# dsplolo.net
KiCad netlist of a schematic drawn in EAGLE
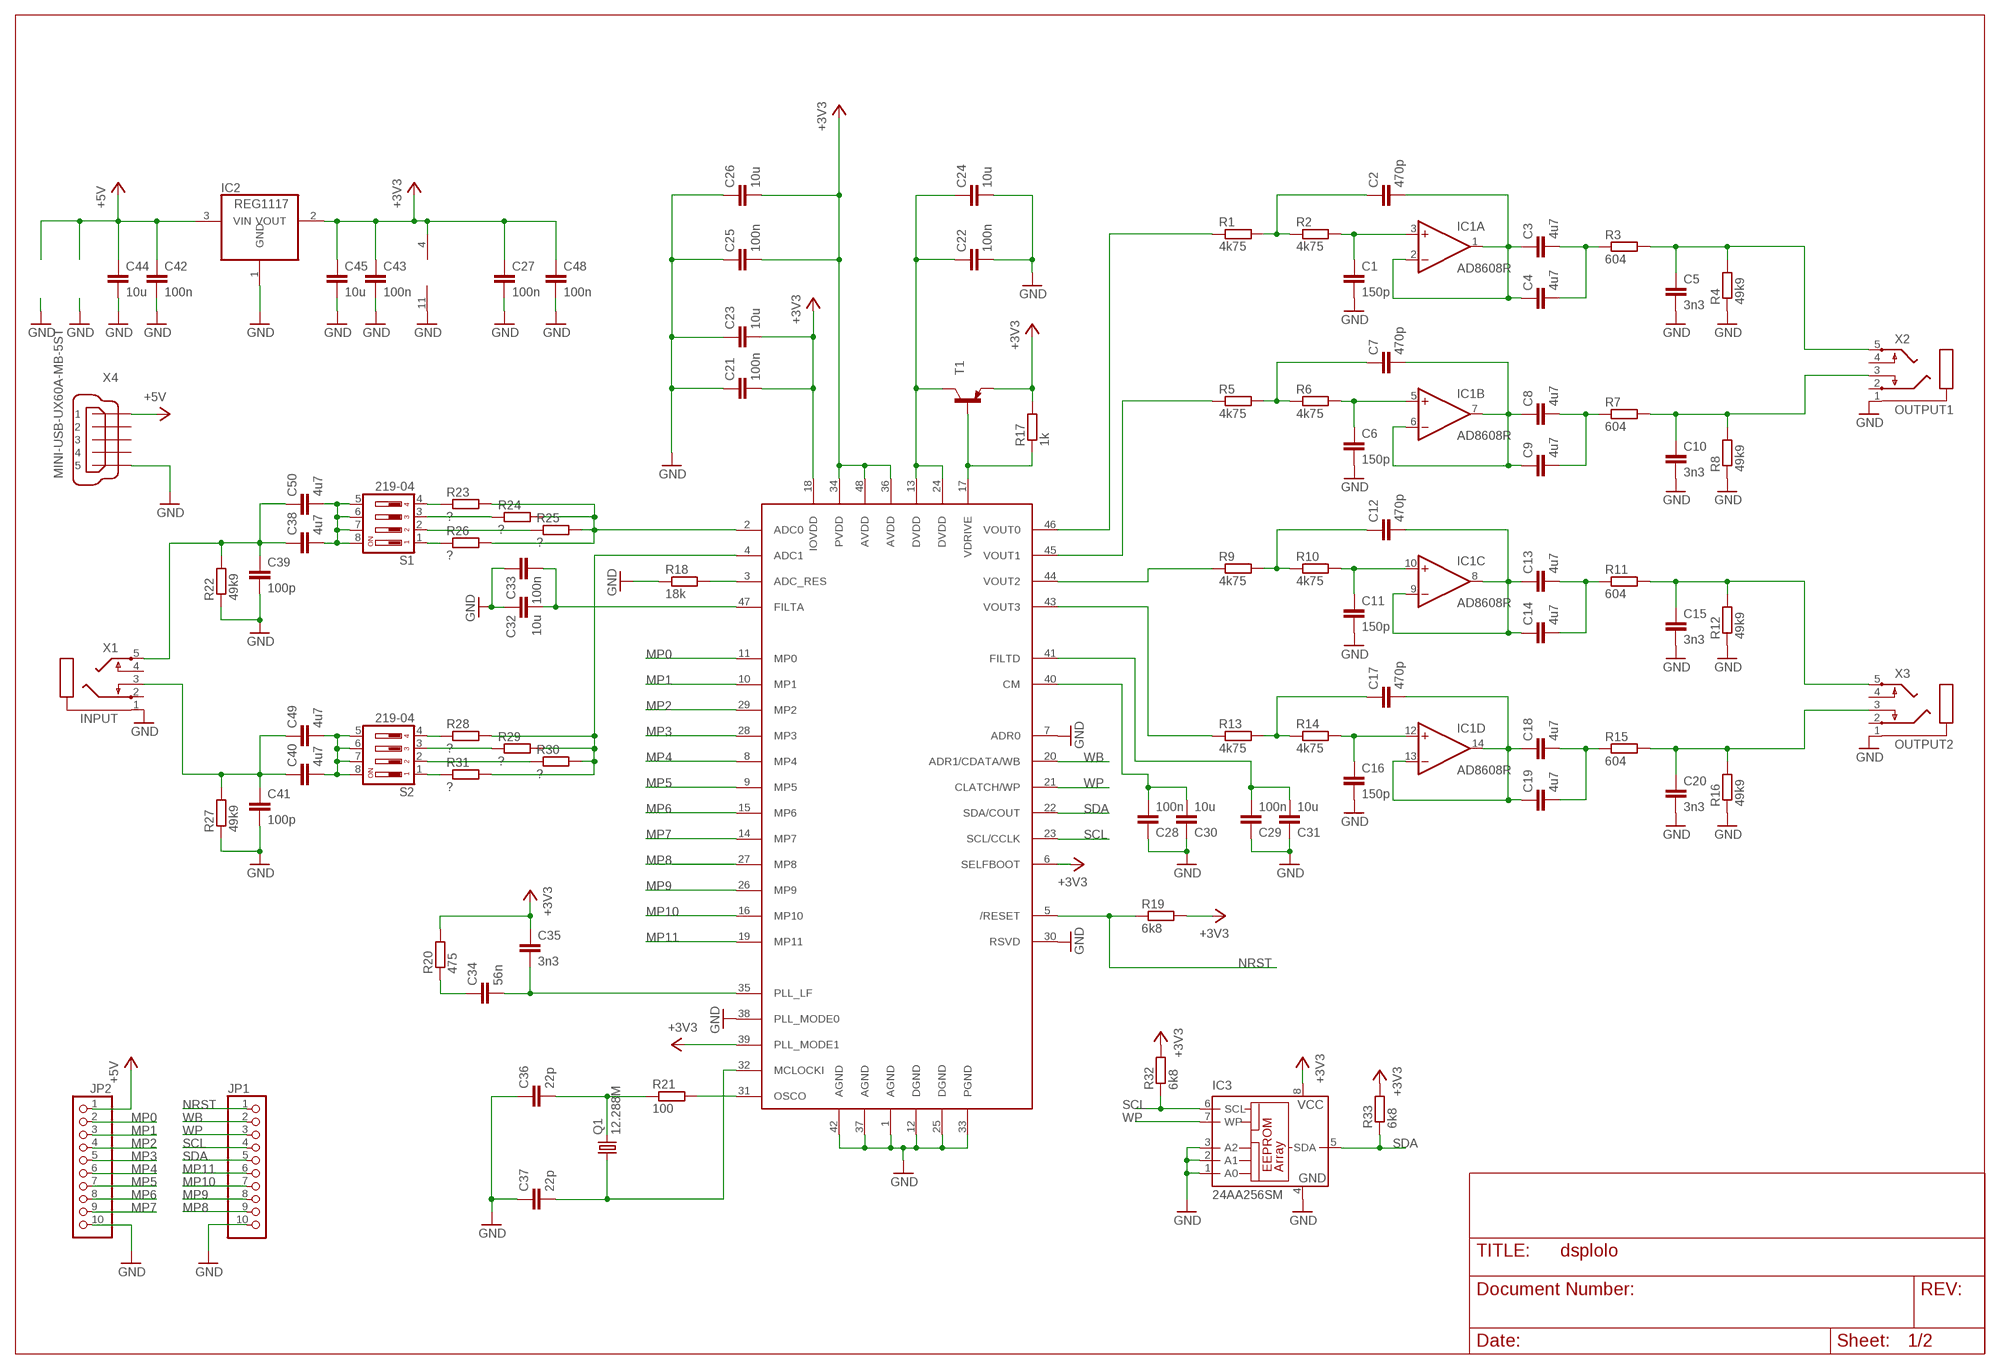
[diagram p0: schematic, sheet 1]
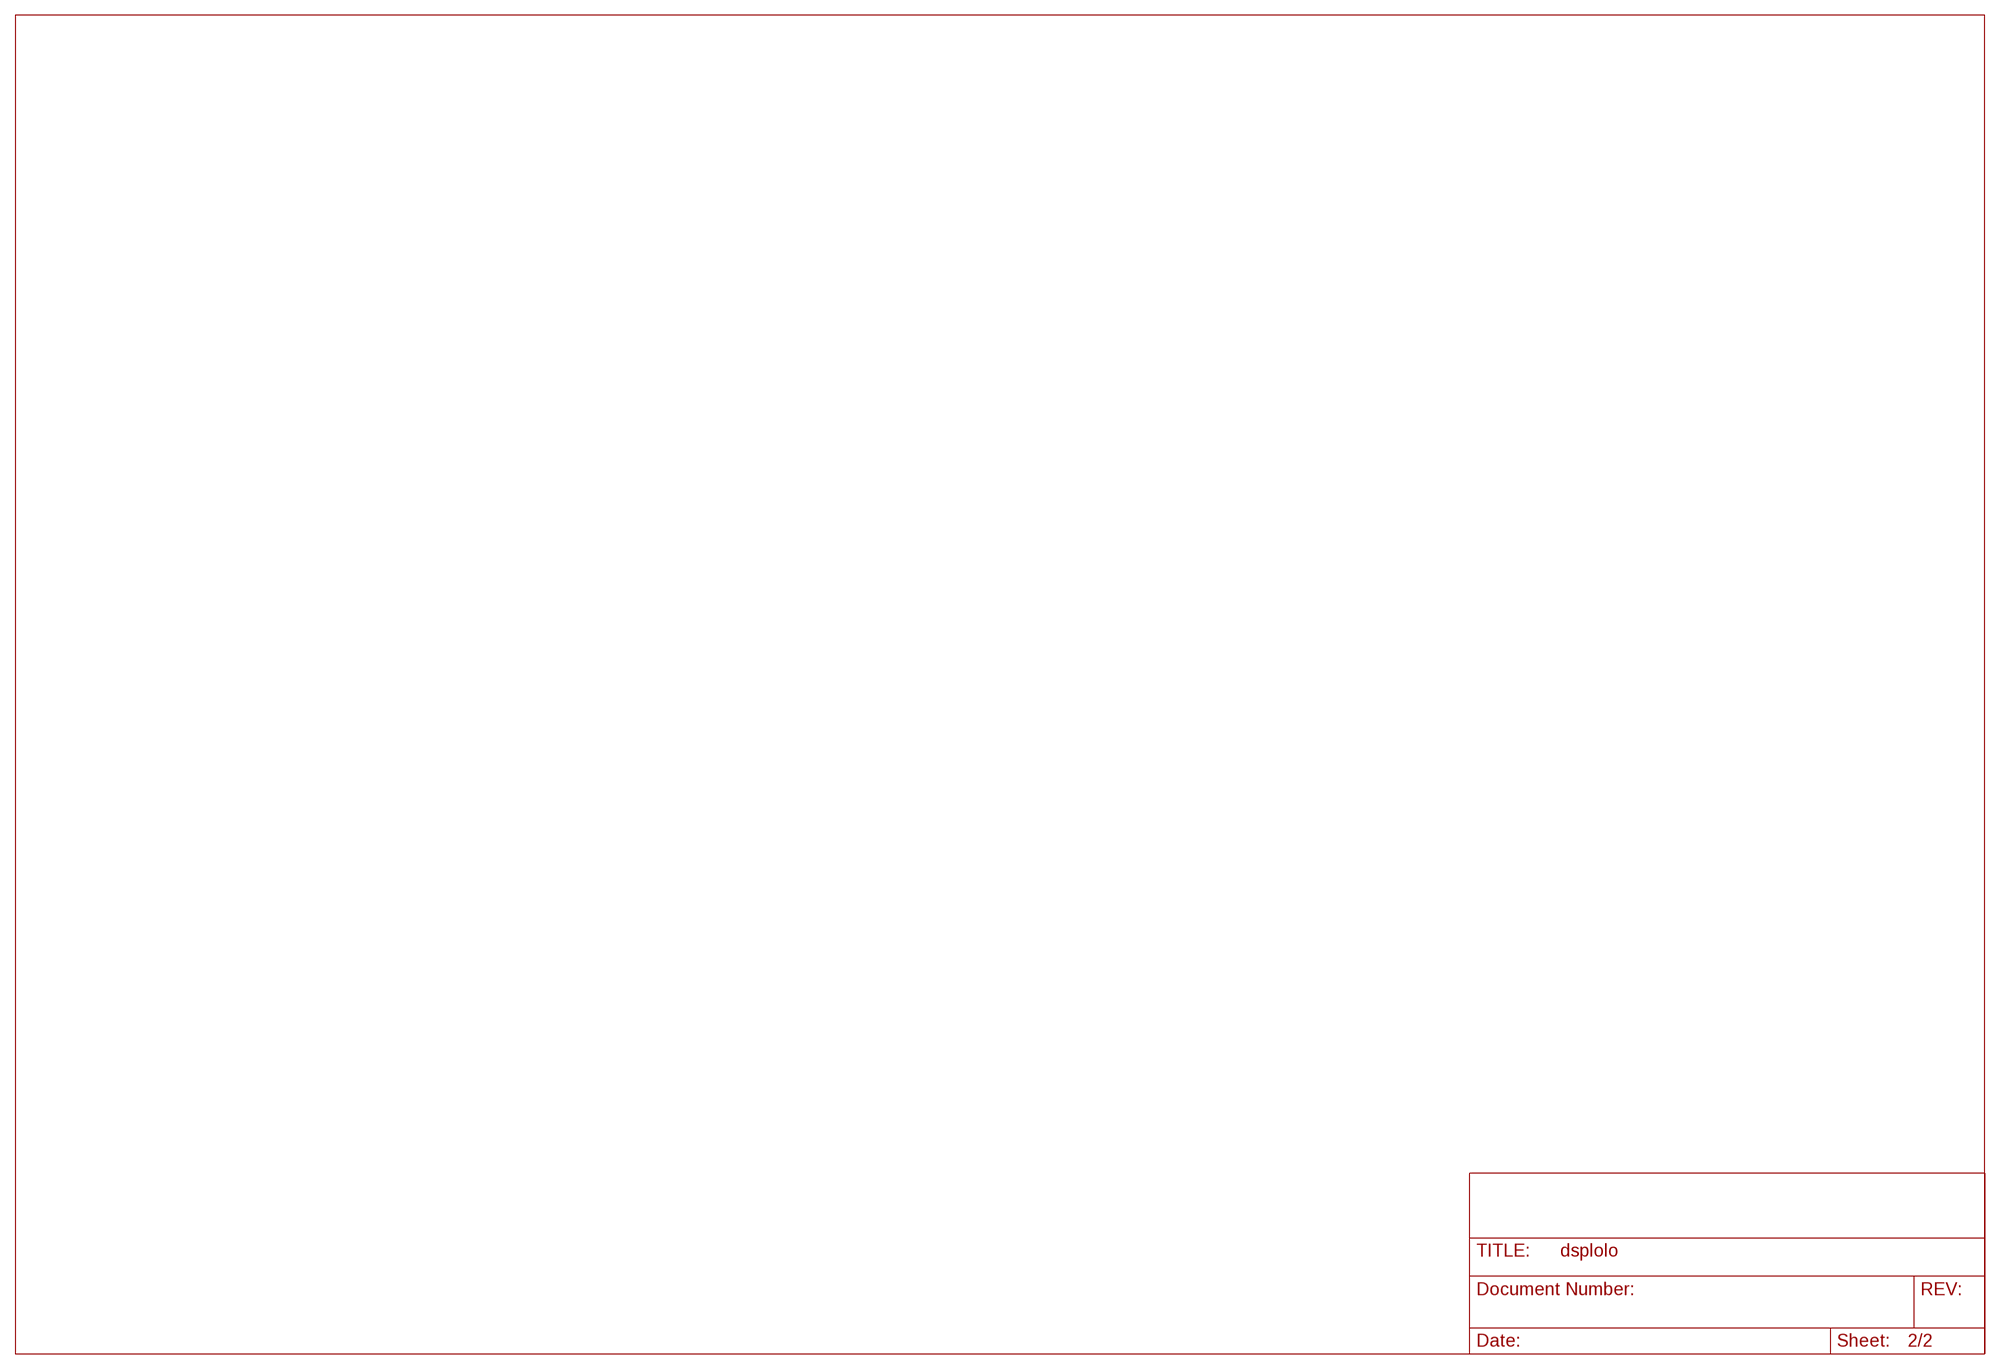
[diagram p1: schematic, sheet 2]

(export (version "E")
  (design (tool "Eeschema 10.0.6"))
  (components
    (comp (ref "C1")
      (value "150p")
      (footprint "eagle-import:C1206")
      (libsource (lib "eagle-import") (part "C-EUC1206"))
    )
    (comp (ref "C2")
      (value "470p")
      (footprint "eagle-import:C1206")
      (libsource (lib "eagle-import") (part "C-EUC1206"))
    )
    (comp (ref "C3")
      (value "4u7")
      (footprint "eagle-import:C1206")
      (libsource (lib "eagle-import") (part "C-EUC1206"))
    )
    (comp (ref "C4")
      (value "4u7")
      (footprint "eagle-import:C1206")
      (libsource (lib "eagle-import") (part "C-EUC1206"))
    )
    (comp (ref "C5")
      (value "3n3")
      (footprint "eagle-import:C1206")
      (libsource (lib "eagle-import") (part "C-EUC1206"))
    )
    (comp (ref "C6")
      (value "150p")
      (footprint "eagle-import:C1206")
      (libsource (lib "eagle-import") (part "C-EUC1206"))
    )
    (comp (ref "C7")
      (value "470p")
      (footprint "eagle-import:C1206")
      (libsource (lib "eagle-import") (part "C-EUC1206"))
    )
    (comp (ref "C8")
      (value "4u7")
      (footprint "eagle-import:C1206")
      (libsource (lib "eagle-import") (part "C-EUC1206"))
    )
    (comp (ref "C9")
      (value "4u7")
      (footprint "eagle-import:C1206")
      (libsource (lib "eagle-import") (part "C-EUC1206"))
    )
    (comp (ref "C10")
      (value "3n3")
      (footprint "eagle-import:C1206")
      (libsource (lib "eagle-import") (part "C-EUC1206"))
    )
    (comp (ref "C11")
      (value "150p")
      (footprint "eagle-import:C1206")
      (libsource (lib "eagle-import") (part "C-EUC1206"))
    )
    (comp (ref "C12")
      (value "470p")
      (footprint "eagle-import:C1206")
      (libsource (lib "eagle-import") (part "C-EUC1206"))
    )
    (comp (ref "C13")
      (value "4u7")
      (footprint "eagle-import:C1206")
      (libsource (lib "eagle-import") (part "C-EUC1206"))
    )
    (comp (ref "C14")
      (value "4u7")
      (footprint "eagle-import:C1206")
      (libsource (lib "eagle-import") (part "C-EUC1206"))
    )
    (comp (ref "C15")
      (value "3n3")
      (footprint "eagle-import:C1206")
      (libsource (lib "eagle-import") (part "C-EUC1206"))
    )
    (comp (ref "C16")
      (value "150p")
      (footprint "eagle-import:C1206")
      (libsource (lib "eagle-import") (part "C-EUC1206"))
    )
    (comp (ref "C17")
      (value "470p")
      (footprint "eagle-import:C1206")
      (libsource (lib "eagle-import") (part "C-EUC1206"))
    )
    (comp (ref "C18")
      (value "4u7")
      (footprint "eagle-import:C1206")
      (libsource (lib "eagle-import") (part "C-EUC1206"))
    )
    (comp (ref "C19")
      (value "4u7")
      (footprint "eagle-import:C1206")
      (libsource (lib "eagle-import") (part "C-EUC1206"))
    )
    (comp (ref "C20")
      (value "3n3")
      (footprint "eagle-import:C1206")
      (libsource (lib "eagle-import") (part "C-EUC1206"))
    )
    (comp (ref "C21")
      (value "100n")
      (footprint "eagle-import:C1206")
      (libsource (lib "eagle-import") (part "resistor_C-EUC1206"))
    )
    (comp (ref "C22")
      (value "100n")
      (footprint "eagle-import:C1206")
      (libsource (lib "eagle-import") (part "resistor_C-EUC1206"))
    )
    (comp (ref "C23")
      (value "10u")
      (footprint "eagle-import:C1206")
      (libsource (lib "eagle-import") (part "resistor_C-EUC1206"))
    )
    (comp (ref "C24")
      (value "10u")
      (footprint "eagle-import:C1206")
      (libsource (lib "eagle-import") (part "resistor_C-EUC1206"))
    )
    (comp (ref "C25")
      (value "100n")
      (footprint "eagle-import:C1206")
      (libsource (lib "eagle-import") (part "resistor_C-EUC1206"))
    )
    (comp (ref "C26")
      (value "10u")
      (footprint "eagle-import:C1206")
      (libsource (lib "eagle-import") (part "resistor_C-EUC1206"))
    )
    (comp (ref "C27")
      (value "100n")
      (footprint "eagle-import:C1206")
      (libsource (lib "eagle-import") (part "resistor_C-EUC1206"))
    )
    (comp (ref "C28")
      (value "100n")
      (footprint "eagle-import:C1206")
      (libsource (lib "eagle-import") (part "resistor_C-EUC1206"))
    )
    (comp (ref "C29")
      (value "100n")
      (footprint "eagle-import:C1206")
      (libsource (lib "eagle-import") (part "resistor_C-EUC1206"))
    )
    (comp (ref "C30")
      (value "10u")
      (footprint "eagle-import:C1206")
      (libsource (lib "eagle-import") (part "resistor_C-EUC1206"))
    )
    (comp (ref "C31")
      (value "10u")
      (footprint "eagle-import:C1206")
      (libsource (lib "eagle-import") (part "resistor_C-EUC1206"))
    )
    (comp (ref "C32")
      (value "10u")
      (footprint "eagle-import:C1206")
      (libsource (lib "eagle-import") (part "resistor_C-EUC1206"))
    )
    (comp (ref "C33")
      (value "100n")
      (footprint "eagle-import:C1206")
      (libsource (lib "eagle-import") (part "resistor_C-EUC1206"))
    )
    (comp (ref "C34")
      (value "56n")
      (footprint "eagle-import:C1206")
      (libsource (lib "eagle-import") (part "resistor_C-EUC1206"))
    )
    (comp (ref "C35")
      (value "3n3")
      (footprint "eagle-import:C1206")
      (libsource (lib "eagle-import") (part "resistor_C-EUC1206"))
    )
    (comp (ref "C36")
      (value "22p")
      (footprint "eagle-import:C1206")
      (libsource (lib "eagle-import") (part "resistor_C-EUC1206"))
    )
    (comp (ref "C37")
      (value "22p")
      (footprint "eagle-import:C1206")
      (libsource (lib "eagle-import") (part "resistor_C-EUC1206"))
    )
    (comp (ref "C38")
      (value "4u7")
      (footprint "eagle-import:C1206")
      (libsource (lib "eagle-import") (part "resistor_C-EUC1206"))
    )
    (comp (ref "C39")
      (value "100p")
      (footprint "eagle-import:C1206")
      (libsource (lib "eagle-import") (part "resistor_C-EUC1206"))
    )
    (comp (ref "C40")
      (value "4u7")
      (footprint "eagle-import:C1206")
      (libsource (lib "eagle-import") (part "resistor_C-EUC1206"))
    )
    (comp (ref "C41")
      (value "100p")
      (footprint "eagle-import:C1206")
      (libsource (lib "eagle-import") (part "resistor_C-EUC1206"))
    )
    (comp (ref "C42")
      (value "100n")
      (footprint "eagle-import:C1206")
      (libsource (lib "eagle-import") (part "resistor_C-EUC1206"))
    )
    (comp (ref "C43")
      (value "100n")
      (footprint "eagle-import:C1206")
      (libsource (lib "eagle-import") (part "resistor_C-EUC1206"))
    )
    (comp (ref "C44")
      (value "10u")
      (footprint "eagle-import:C1206")
      (libsource (lib "eagle-import") (part "resistor_C-EUC1206"))
    )
    (comp (ref "C45")
      (value "10u")
      (footprint "eagle-import:C1206")
      (libsource (lib "eagle-import") (part "resistor_C-EUC1206"))
    )
    (comp (ref "C48")
      (value "100n")
      (footprint "eagle-import:C1206")
      (libsource (lib "eagle-import") (part "resistor_C-EUC1206"))
    )
    (comp (ref "C49")
      (value "4u7")
      (footprint "eagle-import:C1206")
      (libsource (lib "eagle-import") (part "resistor_C-EUC1206"))
    )
    (comp (ref "C50")
      (value "4u7")
      (footprint "eagle-import:C1206")
      (libsource (lib "eagle-import") (part "resistor_C-EUC1206"))
    )
    (comp (ref "IC1")
      (value "AD8608R")
      (footprint "eagle-import:SO-14")
      (libsource (lib "eagle-import") (part "AD8608R"))
    )
    (comp (ref "IC2")
      (value "REG1117")
      (footprint "eagle-import:SOT223")
      (libsource (lib "eagle-import") (part "REG1117"))
    )
    (comp (ref "IC3")
      (value "24AA256SM")
      (footprint "eagle-import:SO-08M")
      (fields (field (name "MF") "MICROCHIP") (field (name "MPN") "24AA128-I/MS"))
      (libsource (lib "eagle-import") (part "24SMAA128"))
    )
    (comp (ref "JP1")
      (value "PINHD-1X10")
      (footprint "eagle-import:1X10")
      (libsource (lib "eagle-import") (part "PINHD-1X10"))
    )
    (comp (ref "JP2")
      (value "PINHD-1X10")
      (footprint "eagle-import:1X10")
      (libsource (lib "eagle-import") (part "PINHD-1X10"))
    )
    (comp (ref "Q1")
      (value "12.288M")
      (footprint "eagle-import:HC49UP")
      (libsource (lib "eagle-import") (part "CRYSTALHC49UP"))
    )
    (comp (ref "R1")
      (value "4k75")
      (footprint "eagle-import:R1206")
      (libsource (lib "eagle-import") (part "R-EU_R1206"))
    )
    (comp (ref "R2")
      (value "4k75")
      (footprint "eagle-import:R1206")
      (libsource (lib "eagle-import") (part "R-EU_R1206"))
    )
    (comp (ref "R3")
      (value "604")
      (footprint "eagle-import:R1206")
      (libsource (lib "eagle-import") (part "R-EU_R1206"))
    )
    (comp (ref "R4")
      (value "49k9")
      (footprint "eagle-import:R1206")
      (libsource (lib "eagle-import") (part "R-EU_R1206"))
    )
    (comp (ref "R5")
      (value "4k75")
      (footprint "eagle-import:R1206")
      (libsource (lib "eagle-import") (part "R-EU_R1206"))
    )
    (comp (ref "R6")
      (value "4k75")
      (footprint "eagle-import:R1206")
      (libsource (lib "eagle-import") (part "R-EU_R1206"))
    )
    (comp (ref "R7")
      (value "604")
      (footprint "eagle-import:R1206")
      (libsource (lib "eagle-import") (part "R-EU_R1206"))
    )
    (comp (ref "R8")
      (value "49k9")
      (footprint "eagle-import:R1206")
      (libsource (lib "eagle-import") (part "R-EU_R1206"))
    )
    (comp (ref "R9")
      (value "4k75")
      (footprint "eagle-import:R1206")
      (libsource (lib "eagle-import") (part "R-EU_R1206"))
    )
    (comp (ref "R10")
      (value "4k75")
      (footprint "eagle-import:R1206")
      (libsource (lib "eagle-import") (part "R-EU_R1206"))
    )
    (comp (ref "R11")
      (value "604")
      (footprint "eagle-import:R1206")
      (libsource (lib "eagle-import") (part "R-EU_R1206"))
    )
    (comp (ref "R12")
      (value "49k9")
      (footprint "eagle-import:R1206")
      (libsource (lib "eagle-import") (part "R-EU_R1206"))
    )
    (comp (ref "R13")
      (value "4k75")
      (footprint "eagle-import:R1206")
      (libsource (lib "eagle-import") (part "R-EU_R1206"))
    )
    (comp (ref "R14")
      (value "4k75")
      (footprint "eagle-import:R1206")
      (libsource (lib "eagle-import") (part "R-EU_R1206"))
    )
    (comp (ref "R15")
      (value "604")
      (footprint "eagle-import:R1206")
      (libsource (lib "eagle-import") (part "R-EU_R1206"))
    )
    (comp (ref "R16")
      (value "49k9")
      (footprint "eagle-import:R1206")
      (libsource (lib "eagle-import") (part "R-EU_R1206"))
    )
    (comp (ref "R17")
      (value "1k")
      (footprint "eagle-import:R1206")
      (libsource (lib "eagle-import") (part "R-EU_R1206"))
    )
    (comp (ref "R18")
      (value "18k")
      (footprint "eagle-import:R1206")
      (libsource (lib "eagle-import") (part "R-EU_R1206"))
    )
    (comp (ref "R19")
      (value "6k8")
      (footprint "eagle-import:R1206")
      (libsource (lib "eagle-import") (part "R-EU_R1206"))
    )
    (comp (ref "R20")
      (value "475")
      (footprint "eagle-import:R1206")
      (libsource (lib "eagle-import") (part "R-EU_R1206"))
    )
    (comp (ref "R21")
      (value "100")
      (footprint "eagle-import:R1206")
      (libsource (lib "eagle-import") (part "R-EU_R1206"))
    )
    (comp (ref "R22")
      (value "49k9")
      (footprint "eagle-import:R1206")
      (libsource (lib "eagle-import") (part "R-EU_R1206"))
    )
    (comp (ref "R23")
      (value "?")
      (footprint "eagle-import:R1206")
      (libsource (lib "eagle-import") (part "R-EU_R1206"))
    )
    (comp (ref "R24")
      (value "?")
      (footprint "eagle-import:R1206")
      (libsource (lib "eagle-import") (part "R-EU_R1206"))
    )
    (comp (ref "R25")
      (value "?")
      (footprint "eagle-import:R1206")
      (libsource (lib "eagle-import") (part "R-EU_R1206"))
    )
    (comp (ref "R26")
      (value "?")
      (footprint "eagle-import:R1206")
      (libsource (lib "eagle-import") (part "R-EU_R1206"))
    )
    (comp (ref "R27")
      (value "49k9")
      (footprint "eagle-import:R1206")
      (libsource (lib "eagle-import") (part "R-EU_R1206"))
    )
    (comp (ref "R28")
      (value "?")
      (footprint "eagle-import:R1206")
      (libsource (lib "eagle-import") (part "R-EU_R1206"))
    )
    (comp (ref "R29")
      (value "?")
      (footprint "eagle-import:R1206")
      (libsource (lib "eagle-import") (part "R-EU_R1206"))
    )
    (comp (ref "R30")
      (value "?")
      (footprint "eagle-import:R1206")
      (libsource (lib "eagle-import") (part "R-EU_R1206"))
    )
    (comp (ref "R31")
      (value "?")
      (footprint "eagle-import:R1206")
      (libsource (lib "eagle-import") (part "R-EU_R1206"))
    )
    (comp (ref "R32")
      (value "6k8")
      (footprint "eagle-import:R1206")
      (libsource (lib "eagle-import") (part "R-EU_R1206"))
    )
    (comp (ref "R33")
      (value "6k8")
      (footprint "eagle-import:R1206")
      (libsource (lib "eagle-import") (part "R-EU_R1206"))
    )
    (comp (ref "S1")
      (value "219-04")
      (footprint "eagle-import:CTS-219-04")
      (libsource (lib "eagle-import") (part "219-04"))
    )
    (comp (ref "S2")
      (value "219-04")
      (footprint "eagle-import:CTS-219-04")
      (libsource (lib "eagle-import") (part "219-04"))
    )
    (comp (ref "T1")
      (value "BC857C-PNP-SOT23-BEC")
      (footprint "eagle-import:SOT23-BEC")
      (libsource (lib "eagle-import") (part "-PNP-SOT23-BECBC857C"))
    )
    (comp (ref "U$1")
      (value "ADAU1701")
      (footprint "eagle-import:LQFP-48")
      (libsource (lib "eagle-import") (part "ADAU1701"))
    )
    (comp (ref "X1")
      (value "INPUT")
      (footprint "eagle-import:STX3100")
      (libsource (lib "eagle-import") (part "STEREOJACK"))
    )
    (comp (ref "X2")
      (value "OUTPUT1")
      (footprint "eagle-import:STX3100")
      (libsource (lib "eagle-import") (part "STEREOJACK"))
    )
    (comp (ref "X3")
      (value "OUTPUT2")
      (footprint "eagle-import:STX3100")
      (libsource (lib "eagle-import") (part "STEREOJACK"))
    )
    (comp (ref "X4")
      (value "MINI-USB-UX60A-MB-5ST")
      (footprint "eagle-import:UX60A-MB-5ST")
      (libsource (lib "eagle-import") (part "MINI-USB-UX60A-MB-5ST"))
    )
  )
  (nets
    (net (code "1") (name "+3V3") (class "Default")
      (node (ref "C21") (pin "2") (pinfunction "2_2") (pintype "passive"))
      (node (ref "C23") (pin "2") (pinfunction "2_2") (pintype "passive"))
      (node (ref "C25") (pin "2") (pinfunction "2_2") (pintype "passive"))
      (node (ref "C26") (pin "2") (pinfunction "2_2") (pintype "passive"))
      (node (ref "C27") (pin "1") (pinfunction "1_1") (pintype "passive"))
      (node (ref "C35") (pin "1") (pinfunction "1_1") (pintype "passive"))
      (node (ref "C43") (pin "1") (pinfunction "1_1") (pintype "passive"))
      (node (ref "C45") (pin "1") (pinfunction "1_1") (pintype "passive"))
      (node (ref "C48") (pin "1") (pinfunction "1_1") (pintype "passive"))
      (node (ref "IC1") (pin "4") (pinfunction "V+_4") (pintype "power_in"))
      (node (ref "IC2") (pin "2") (pinfunction "VOUT_2") (pintype "output"))
      (node (ref "IC3") (pin "8") (pinfunction "VCC_8") (pintype "power_in"))
      (node (ref "R17") (pin "2") (pinfunction "2_2") (pintype "passive"))
      (node (ref "R19") (pin "2") (pinfunction "2_2") (pintype "passive"))
      (node (ref "R20") (pin "2") (pinfunction "2_2") (pintype "passive"))
      (node (ref "R32") (pin "2") (pinfunction "2_2") (pintype "passive"))
      (node (ref "R33") (pin "2") (pinfunction "2_2") (pintype "passive"))
      (node (ref "T1") (pin "E") (pinfunction "E_E") (pintype "passive"))
      (node (ref "U$1") (pin "18") (pinfunction "IOVDD_18") (pintype "bidirectional"))
      (node (ref "U$1") (pin "34") (pinfunction "PVDD_34") (pintype "bidirectional"))
      (node (ref "U$1") (pin "36") (pinfunction "AVDD_36") (pintype "bidirectional"))
      (node (ref "U$1") (pin "39") (pinfunction "PLL_MODE1_39") (pintype "bidirectional"))
      (node (ref "U$1") (pin "48") (pinfunction "AVDD_48") (pintype "bidirectional"))
      (node (ref "U$1") (pin "6") (pinfunction "SELFBOOT_6") (pintype "bidirectional"))
    )
    (net (code "2") (name "+5V") (class "Default")
      (node (ref "C42") (pin "1") (pinfunction "1_1") (pintype "passive"))
      (node (ref "C44") (pin "1") (pinfunction "1_1") (pintype "passive"))
      (node (ref "IC2") (pin "3") (pinfunction "VIN_3") (pintype "input"))
      (node (ref "JP2") (pin "1") (pinfunction "1_1") (pintype "passive"))
      (node (ref "X4") (pin "1") (pinfunction "1_1") (pintype "input"))
    )
    (net (code "3") (name "GND") (class "Default")
      (node (ref "C1") (pin "2") (pinfunction "2_2") (pintype "passive"))
      (node (ref "C10") (pin "2") (pinfunction "2_2") (pintype "passive"))
      (node (ref "C11") (pin "2") (pinfunction "2_2") (pintype "passive"))
      (node (ref "C15") (pin "2") (pinfunction "2_2") (pintype "passive"))
      (node (ref "C16") (pin "2") (pinfunction "2_2") (pintype "passive"))
      (node (ref "C20") (pin "2") (pinfunction "2_2") (pintype "passive"))
      (node (ref "C21") (pin "1") (pinfunction "1_1") (pintype "passive"))
      (node (ref "C22") (pin "2") (pinfunction "2_2") (pintype "passive"))
      (node (ref "C23") (pin "1") (pinfunction "1_1") (pintype "passive"))
      (node (ref "C24") (pin "2") (pinfunction "2_2") (pintype "passive"))
      (node (ref "C25") (pin "1") (pinfunction "1_1") (pintype "passive"))
      (node (ref "C26") (pin "1") (pinfunction "1_1") (pintype "passive"))
      (node (ref "C27") (pin "2") (pinfunction "2_2") (pintype "passive"))
      (node (ref "C28") (pin "1") (pinfunction "1_1") (pintype "passive"))
      (node (ref "C29") (pin "1") (pinfunction "1_1") (pintype "passive"))
      (node (ref "C30") (pin "1") (pinfunction "1_1") (pintype "passive"))
      (node (ref "C31") (pin "1") (pinfunction "1_1") (pintype "passive"))
      (node (ref "C32") (pin "1") (pinfunction "1_1") (pintype "passive"))
      (node (ref "C33") (pin "1") (pinfunction "1_1") (pintype "passive"))
      (node (ref "C36") (pin "1") (pinfunction "1_1") (pintype "passive"))
      (node (ref "C37") (pin "1") (pinfunction "1_1") (pintype "passive"))
      (node (ref "C39") (pin "2") (pinfunction "2_2") (pintype "passive"))
      (node (ref "C41") (pin "2") (pinfunction "2_2") (pintype "passive"))
      (node (ref "C42") (pin "2") (pinfunction "2_2") (pintype "passive"))
      (node (ref "C43") (pin "2") (pinfunction "2_2") (pintype "passive"))
      (node (ref "C44") (pin "2") (pinfunction "2_2") (pintype "passive"))
      (node (ref "C45") (pin "2") (pinfunction "2_2") (pintype "passive"))
      (node (ref "C48") (pin "2") (pinfunction "2_2") (pintype "passive"))
      (node (ref "C5") (pin "2") (pinfunction "2_2") (pintype "passive"))
      (node (ref "C6") (pin "2") (pinfunction "2_2") (pintype "passive"))
      (node (ref "IC1") (pin "11") (pinfunction "V-_11") (pintype "power_in"))
      (node (ref "IC2") (pin "1") (pinfunction "GND_1") (pintype "power_in"))
      (node (ref "IC3") (pin "1") (pinfunction "A0_1") (pintype "input"))
      (node (ref "IC3") (pin "2") (pinfunction "A1_2") (pintype "input"))
      (node (ref "IC3") (pin "3") (pinfunction "A2_3") (pintype "input"))
      (node (ref "IC3") (pin "4") (pinfunction "GND_4") (pintype "power_in"))
      (node (ref "JP1") (pin "10") (pinfunction "10_10") (pintype "passive"))
      (node (ref "JP2") (pin "10") (pinfunction "10_10") (pintype "passive"))
      (node (ref "R12") (pin "1") (pinfunction "1_1") (pintype "passive"))
      (node (ref "R16") (pin "1") (pinfunction "1_1") (pintype "passive"))
      (node (ref "R18") (pin "1") (pinfunction "1_1") (pintype "passive"))
      (node (ref "R22") (pin "1") (pinfunction "1_1") (pintype "passive"))
      (node (ref "R27") (pin "1") (pinfunction "1_1") (pintype "passive"))
      (node (ref "R4") (pin "1") (pinfunction "1_1") (pintype "passive"))
      (node (ref "R8") (pin "1") (pinfunction "1_1") (pintype "passive"))
      (node (ref "U$1") (pin "1") (pinfunction "AGND_1") (pintype "bidirectional"))
      (node (ref "U$1") (pin "12") (pinfunction "DGND_12") (pintype "bidirectional"))
      (node (ref "U$1") (pin "25") (pinfunction "DGND_25") (pintype "bidirectional"))
      (node (ref "U$1") (pin "30") (pinfunction "RSVD_30") (pintype "bidirectional"))
      (node (ref "U$1") (pin "33") (pinfunction "PGND_33") (pintype "bidirectional"))
      (node (ref "U$1") (pin "37") (pinfunction "AGND_37") (pintype "bidirectional"))
      (node (ref "U$1") (pin "38") (pinfunction "PLL_MODE0_38") (pintype "bidirectional"))
      (node (ref "U$1") (pin "42") (pinfunction "AGND_42") (pintype "bidirectional"))
      (node (ref "U$1") (pin "7") (pinfunction "ADR0_7") (pintype "bidirectional"))
      (node (ref "X1") (pin "1") (pinfunction "1_1") (pintype "passive"))
      (node (ref "X2") (pin "1") (pinfunction "1_1") (pintype "passive"))
      (node (ref "X3") (pin "1") (pinfunction "1_1") (pintype "passive"))
      (node (ref "X4") (pin "5") (pinfunction "5_5") (pintype "input"))
    )
    (net (code "4") (name "MP0") (class "Default")
      (node (ref "JP2") (pin "2") (pinfunction "2_2") (pintype "passive"))
      (node (ref "U$1") (pin "11") (pinfunction "MP0_11") (pintype "bidirectional"))
    )
    (net (code "5") (name "MP1") (class "Default")
      (node (ref "JP2") (pin "3") (pinfunction "3_3") (pintype "passive"))
      (node (ref "U$1") (pin "10") (pinfunction "MP1_10") (pintype "bidirectional"))
    )
    (net (code "6") (name "MP2") (class "Default")
      (node (ref "JP2") (pin "4") (pinfunction "4_4") (pintype "passive"))
      (node (ref "U$1") (pin "29") (pinfunction "MP2_29") (pintype "bidirectional"))
    )
    (net (code "7") (name "MP3") (class "Default")
      (node (ref "JP2") (pin "5") (pinfunction "5_5") (pintype "passive"))
      (node (ref "U$1") (pin "28") (pinfunction "MP3_28") (pintype "bidirectional"))
    )
    (net (code "8") (name "MP4") (class "Default")
      (node (ref "JP2") (pin "6") (pinfunction "6_6") (pintype "passive"))
      (node (ref "U$1") (pin "8") (pinfunction "MP4_8") (pintype "bidirectional"))
    )
    (net (code "9") (name "MP5") (class "Default")
      (node (ref "JP2") (pin "7") (pinfunction "7_7") (pintype "passive"))
      (node (ref "U$1") (pin "9") (pinfunction "MP5_9") (pintype "bidirectional"))
    )
    (net (code "10") (name "MP6") (class "Default")
      (node (ref "JP2") (pin "8") (pinfunction "8_8") (pintype "passive"))
      (node (ref "U$1") (pin "15") (pinfunction "MP6_15") (pintype "bidirectional"))
    )
    (net (code "11") (name "MP7") (class "Default")
      (node (ref "JP2") (pin "9") (pinfunction "9_9") (pintype "passive"))
      (node (ref "U$1") (pin "14") (pinfunction "MP7_14") (pintype "bidirectional"))
    )
    (net (code "12") (name "MP8") (class "Default")
      (node (ref "JP1") (pin "9") (pinfunction "9_9") (pintype "passive"))
      (node (ref "U$1") (pin "27") (pinfunction "MP8_27") (pintype "bidirectional"))
    )
    (net (code "13") (name "MP9") (class "Default")
      (node (ref "JP1") (pin "8") (pinfunction "8_8") (pintype "passive"))
      (node (ref "U$1") (pin "26") (pinfunction "MP9_26") (pintype "bidirectional"))
    )
    (net (code "14") (name "MP10") (class "Default")
      (node (ref "JP1") (pin "7") (pinfunction "7_7") (pintype "passive"))
      (node (ref "U$1") (pin "16") (pinfunction "MP10_16") (pintype "bidirectional"))
    )
    (net (code "15") (name "MP11") (class "Default")
      (node (ref "JP1") (pin "6") (pinfunction "6_6") (pintype "passive"))
      (node (ref "U$1") (pin "19") (pinfunction "MP11_19") (pintype "bidirectional"))
    )
    (net (code "16") (name "NRST") (class "Default")
      (node (ref "JP1") (pin "1") (pinfunction "1_1") (pintype "passive"))
      (node (ref "R19") (pin "1") (pinfunction "1_1") (pintype "passive"))
      (node (ref "U$1") (pin "5") (pinfunction "/RESET_5") (pintype "bidirectional"))
    )
    (net (code "17") (name "Net-(C2-Pad1)") (class "Default")
      (node (ref "C2") (pin "1") (pinfunction "1_1") (pintype "passive"))
      (node (ref "R1") (pin "2") (pinfunction "2_2") (pintype "passive"))
      (node (ref "R2") (pin "1") (pinfunction "1_1") (pintype "passive"))
    )
    (net (code "18") (name "Net-(C3-Pad2)") (class "Default")
      (node (ref "C3") (pin "2") (pinfunction "2_2") (pintype "passive"))
      (node (ref "C4") (pin "2") (pinfunction "2_2") (pintype "passive"))
      (node (ref "R3") (pin "1") (pinfunction "1_1") (pintype "passive"))
    )
    (net (code "19") (name "Net-(C5-Pad1)") (class "Default")
      (node (ref "C5") (pin "1") (pinfunction "1_1") (pintype "passive"))
      (node (ref "R3") (pin "2") (pinfunction "2_2") (pintype "passive"))
      (node (ref "R4") (pin "2") (pinfunction "2_2") (pintype "passive"))
      (node (ref "X2") (pin "5") (pinfunction "5_5") (pintype "passive"))
    )
    (net (code "20") (name "Net-(C7-Pad1)") (class "Default")
      (node (ref "C7") (pin "1") (pinfunction "1_1") (pintype "passive"))
      (node (ref "R5") (pin "2") (pinfunction "2_2") (pintype "passive"))
      (node (ref "R6") (pin "1") (pinfunction "1_1") (pintype "passive"))
    )
    (net (code "21") (name "Net-(C8-Pad2)") (class "Default")
      (node (ref "C8") (pin "2") (pinfunction "2_2") (pintype "passive"))
      (node (ref "C9") (pin "2") (pinfunction "2_2") (pintype "passive"))
      (node (ref "R7") (pin "1") (pinfunction "1_1") (pintype "passive"))
    )
    (net (code "22") (name "Net-(C10-Pad1)") (class "Default")
      (node (ref "C10") (pin "1") (pinfunction "1_1") (pintype "passive"))
      (node (ref "R7") (pin "2") (pinfunction "2_2") (pintype "passive"))
      (node (ref "R8") (pin "2") (pinfunction "2_2") (pintype "passive"))
      (node (ref "X2") (pin "3") (pinfunction "3_3") (pintype "passive"))
    )
    (net (code "23") (name "Net-(C12-Pad1)") (class "Default")
      (node (ref "C12") (pin "1") (pinfunction "1_1") (pintype "passive"))
      (node (ref "R10") (pin "1") (pinfunction "1_1") (pintype "passive"))
      (node (ref "R9") (pin "2") (pinfunction "2_2") (pintype "passive"))
    )
    (net (code "24") (name "Net-(C13-Pad2)") (class "Default")
      (node (ref "C13") (pin "2") (pinfunction "2_2") (pintype "passive"))
      (node (ref "C14") (pin "2") (pinfunction "2_2") (pintype "passive"))
      (node (ref "R11") (pin "1") (pinfunction "1_1") (pintype "passive"))
    )
    (net (code "25") (name "Net-(C15-Pad1)") (class "Default")
      (node (ref "C15") (pin "1") (pinfunction "1_1") (pintype "passive"))
      (node (ref "R11") (pin "2") (pinfunction "2_2") (pintype "passive"))
      (node (ref "R12") (pin "2") (pinfunction "2_2") (pintype "passive"))
      (node (ref "X3") (pin "5") (pinfunction "5_5") (pintype "passive"))
    )
    (net (code "26") (name "Net-(C17-Pad1)") (class "Default")
      (node (ref "C17") (pin "1") (pinfunction "1_1") (pintype "passive"))
      (node (ref "R13") (pin "2") (pinfunction "2_2") (pintype "passive"))
      (node (ref "R14") (pin "1") (pinfunction "1_1") (pintype "passive"))
    )
    (net (code "27") (name "Net-(C18-Pad2)") (class "Default")
      (node (ref "C18") (pin "2") (pinfunction "2_2") (pintype "passive"))
      (node (ref "C19") (pin "2") (pinfunction "2_2") (pintype "passive"))
      (node (ref "R15") (pin "1") (pinfunction "1_1") (pintype "passive"))
    )
    (net (code "28") (name "Net-(C20-Pad1)") (class "Default")
      (node (ref "C20") (pin "1") (pinfunction "1_1") (pintype "passive"))
      (node (ref "R15") (pin "2") (pinfunction "2_2") (pintype "passive"))
      (node (ref "R16") (pin "2") (pinfunction "2_2") (pintype "passive"))
      (node (ref "X3") (pin "3") (pinfunction "3_3") (pintype "passive"))
    )
    (net (code "29") (name "Net-(C22-Pad1)") (class "Default")
      (node (ref "C22") (pin "1") (pinfunction "1_1") (pintype "passive"))
      (node (ref "C24") (pin "1") (pinfunction "1_1") (pintype "passive"))
      (node (ref "T1") (pin "C") (pinfunction "C_C") (pintype "passive"))
      (node (ref "U$1") (pin "13") (pinfunction "DVDD_13") (pintype "bidirectional"))
      (node (ref "U$1") (pin "24") (pinfunction "DVDD_24") (pintype "bidirectional"))
    )
    (net (code "30") (name "Net-(C34-Pad1)") (class "Default")
      (node (ref "C34") (pin "1") (pinfunction "1_1") (pintype "passive"))
      (node (ref "R20") (pin "1") (pinfunction "1_1") (pintype "passive"))
    )
    (net (code "31") (name "Net-(C36-Pad2)") (class "Default")
      (node (ref "C36") (pin "2") (pinfunction "2_2") (pintype "passive"))
      (node (ref "Q1") (pin "2") (pinfunction "2_2") (pintype "passive"))
      (node (ref "R21") (pin "1") (pinfunction "1_1") (pintype "passive"))
    )
    (net (code "32") (name "Net-(C38-Pad1)") (class "Default")
      (node (ref "C38") (pin "1") (pinfunction "1_1") (pintype "passive"))
      (node (ref "C39") (pin "1") (pinfunction "1_1") (pintype "passive"))
      (node (ref "C50") (pin "1") (pinfunction "1_1") (pintype "passive"))
      (node (ref "R22") (pin "2") (pinfunction "2_2") (pintype "passive"))
      (node (ref "X1") (pin "5") (pinfunction "5_5") (pintype "passive"))
    )
    (net (code "33") (name "Net-(C38-Pad2)") (class "Default")
      (node (ref "C38") (pin "2") (pinfunction "2_2") (pintype "passive"))
      (node (ref "C50") (pin "2") (pinfunction "2_2") (pintype "passive"))
      (node (ref "S1") (pin "5") (pinfunction "5_5") (pintype "passive"))
      (node (ref "S1") (pin "6") (pinfunction "6_6") (pintype "passive"))
      (node (ref "S1") (pin "7") (pinfunction "7_7") (pintype "passive"))
      (node (ref "S1") (pin "8") (pinfunction "8_8") (pintype "passive"))
    )
    (net (code "34") (name "Net-(C40-Pad1)") (class "Default")
      (node (ref "C40") (pin "1") (pinfunction "1_1") (pintype "passive"))
      (node (ref "C41") (pin "1") (pinfunction "1_1") (pintype "passive"))
      (node (ref "C49") (pin "1") (pinfunction "1_1") (pintype "passive"))
      (node (ref "R27") (pin "2") (pinfunction "2_2") (pintype "passive"))
      (node (ref "X1") (pin "3") (pinfunction "3_3") (pintype "passive"))
    )
    (net (code "35") (name "Net-(C40-Pad2)") (class "Default")
      (node (ref "C40") (pin "2") (pinfunction "2_2") (pintype "passive"))
      (node (ref "C49") (pin "2") (pinfunction "2_2") (pintype "passive"))
      (node (ref "S2") (pin "5") (pinfunction "5_5") (pintype "passive"))
      (node (ref "S2") (pin "6") (pinfunction "6_6") (pintype "passive"))
      (node (ref "S2") (pin "7") (pinfunction "7_7") (pintype "passive"))
      (node (ref "S2") (pin "8") (pinfunction "8_8") (pintype "passive"))
    )
    (net (code "36") (name "Net-(IC1A-+IN)") (class "Default")
      (node (ref "C1") (pin "1") (pinfunction "1_1") (pintype "passive"))
      (node (ref "IC1") (pin "3") (pinfunction "+IN_3") (pintype "input"))
      (node (ref "R2") (pin "2") (pinfunction "2_2") (pintype "passive"))
    )
    (net (code "37") (name "Net-(IC1A--IN)") (class "Default")
      (node (ref "C2") (pin "2") (pinfunction "2_2") (pintype "passive"))
      (node (ref "C3") (pin "1") (pinfunction "1_1") (pintype "passive"))
      (node (ref "C4") (pin "1") (pinfunction "1_1") (pintype "passive"))
      (node (ref "IC1") (pin "1") (pinfunction "OUT_1") (pintype "output"))
      (node (ref "IC1") (pin "2") (pinfunction "-IN_2") (pintype "input"))
    )
    (net (code "38") (name "Net-(IC1B-+IN)") (class "Default")
      (node (ref "C6") (pin "1") (pinfunction "1_1") (pintype "passive"))
      (node (ref "IC1") (pin "5") (pinfunction "+IN_5") (pintype "input"))
      (node (ref "R6") (pin "2") (pinfunction "2_2") (pintype "passive"))
    )
    (net (code "39") (name "Net-(IC1B--IN)") (class "Default")
      (node (ref "C7") (pin "2") (pinfunction "2_2") (pintype "passive"))
      (node (ref "C8") (pin "1") (pinfunction "1_1") (pintype "passive"))
      (node (ref "C9") (pin "1") (pinfunction "1_1") (pintype "passive"))
      (node (ref "IC1") (pin "6") (pinfunction "-IN_6") (pintype "input"))
      (node (ref "IC1") (pin "7") (pinfunction "OUT_7") (pintype "output"))
    )
    (net (code "40") (name "Net-(IC1C-+IN)") (class "Default")
      (node (ref "C11") (pin "1") (pinfunction "1_1") (pintype "passive"))
      (node (ref "IC1") (pin "10") (pinfunction "+IN_10") (pintype "input"))
      (node (ref "R10") (pin "2") (pinfunction "2_2") (pintype "passive"))
    )
    (net (code "41") (name "Net-(IC1C--IN)") (class "Default")
      (node (ref "C12") (pin "2") (pinfunction "2_2") (pintype "passive"))
      (node (ref "C13") (pin "1") (pinfunction "1_1") (pintype "passive"))
      (node (ref "C14") (pin "1") (pinfunction "1_1") (pintype "passive"))
      (node (ref "IC1") (pin "8") (pinfunction "OUT_8") (pintype "output"))
      (node (ref "IC1") (pin "9") (pinfunction "-IN_9") (pintype "input"))
    )
    (net (code "42") (name "Net-(IC1D-+IN)") (class "Default")
      (node (ref "C16") (pin "1") (pinfunction "1_1") (pintype "passive"))
      (node (ref "IC1") (pin "12") (pinfunction "+IN_12") (pintype "input"))
      (node (ref "R14") (pin "2") (pinfunction "2_2") (pintype "passive"))
    )
    (net (code "43") (name "Net-(IC1D--IN)") (class "Default")
      (node (ref "C17") (pin "2") (pinfunction "2_2") (pintype "passive"))
      (node (ref "C18") (pin "1") (pinfunction "1_1") (pintype "passive"))
      (node (ref "C19") (pin "1") (pinfunction "1_1") (pintype "passive"))
      (node (ref "IC1") (pin "13") (pinfunction "-IN_13") (pintype "input"))
      (node (ref "IC1") (pin "14") (pinfunction "OUT_14") (pintype "output"))
    )
    (net (code "44") (name "Net-(R23-Pad1)") (class "Default")
      (node (ref "R23") (pin "1") (pinfunction "1_1") (pintype "passive"))
      (node (ref "S1") (pin "4") (pinfunction "4_4") (pintype "passive"))
    )
    (net (code "45") (name "Net-(R24-Pad1)") (class "Default")
      (node (ref "R24") (pin "1") (pinfunction "1_1") (pintype "passive"))
      (node (ref "S1") (pin "3") (pinfunction "3_3") (pintype "passive"))
    )
    (net (code "46") (name "Net-(R25-Pad1)") (class "Default")
      (node (ref "R25") (pin "1") (pinfunction "1_1") (pintype "passive"))
      (node (ref "S1") (pin "2") (pinfunction "2_2") (pintype "passive"))
    )
    (net (code "47") (name "Net-(R26-Pad1)") (class "Default")
      (node (ref "R26") (pin "1") (pinfunction "1_1") (pintype "passive"))
      (node (ref "S1") (pin "1") (pinfunction "1_1") (pintype "passive"))
    )
    (net (code "48") (name "Net-(R28-Pad1)") (class "Default")
      (node (ref "R28") (pin "1") (pinfunction "1_1") (pintype "passive"))
      (node (ref "S2") (pin "4") (pinfunction "4_4") (pintype "passive"))
    )
    (net (code "49") (name "Net-(R29-Pad1)") (class "Default")
      (node (ref "R29") (pin "1") (pinfunction "1_1") (pintype "passive"))
      (node (ref "S2") (pin "3") (pinfunction "3_3") (pintype "passive"))
    )
    (net (code "50") (name "Net-(R30-Pad1)") (class "Default")
      (node (ref "R30") (pin "1") (pinfunction "1_1") (pintype "passive"))
      (node (ref "S2") (pin "2") (pinfunction "2_2") (pintype "passive"))
    )
    (net (code "51") (name "Net-(R31-Pad1)") (class "Default")
      (node (ref "R31") (pin "1") (pinfunction "1_1") (pintype "passive"))
      (node (ref "S2") (pin "1") (pinfunction "1_1") (pintype "passive"))
    )
    (net (code "52") (name "Net-(U$1-ADC0)") (class "Default")
      (node (ref "R23") (pin "2") (pinfunction "2_2") (pintype "passive"))
      (node (ref "R24") (pin "2") (pinfunction "2_2") (pintype "passive"))
      (node (ref "R25") (pin "2") (pinfunction "2_2") (pintype "passive"))
      (node (ref "R26") (pin "2") (pinfunction "2_2") (pintype "passive"))
      (node (ref "U$1") (pin "2") (pinfunction "ADC0_2") (pintype "bidirectional"))
    )
    (net (code "53") (name "Net-(U$1-ADC1)") (class "Default")
      (node (ref "R28") (pin "2") (pinfunction "2_2") (pintype "passive"))
      (node (ref "R29") (pin "2") (pinfunction "2_2") (pintype "passive"))
      (node (ref "R30") (pin "2") (pinfunction "2_2") (pintype "passive"))
      (node (ref "R31") (pin "2") (pinfunction "2_2") (pintype "passive"))
      (node (ref "U$1") (pin "4") (pinfunction "ADC1_4") (pintype "bidirectional"))
    )
    (net (code "54") (name "Net-(U$1-ADC_RES)") (class "Default")
      (node (ref "R18") (pin "2") (pinfunction "2_2") (pintype "passive"))
      (node (ref "U$1") (pin "3") (pinfunction "ADC_RES_3") (pintype "bidirectional"))
    )
    (net (code "55") (name "Net-(U$1-CM)") (class "Default")
      (node (ref "C28") (pin "2") (pinfunction "2_2") (pintype "passive"))
      (node (ref "C30") (pin "2") (pinfunction "2_2") (pintype "passive"))
      (node (ref "U$1") (pin "40") (pinfunction "CM_40") (pintype "bidirectional"))
    )
    (net (code "56") (name "Net-(U$1-FILTA)") (class "Default")
      (node (ref "C32") (pin "2") (pinfunction "2_2") (pintype "passive"))
      (node (ref "C33") (pin "2") (pinfunction "2_2") (pintype "passive"))
      (node (ref "U$1") (pin "47") (pinfunction "FILTA_47") (pintype "bidirectional"))
    )
    (net (code "57") (name "Net-(U$1-FILTD)") (class "Default")
      (node (ref "C29") (pin "2") (pinfunction "2_2") (pintype "passive"))
      (node (ref "C31") (pin "2") (pinfunction "2_2") (pintype "passive"))
      (node (ref "U$1") (pin "41") (pinfunction "FILTD_41") (pintype "bidirectional"))
    )
    (net (code "58") (name "Net-(U$1-MCLOCKI)") (class "Default")
      (node (ref "C37") (pin "2") (pinfunction "2_2") (pintype "passive"))
      (node (ref "Q1") (pin "1") (pinfunction "1_1") (pintype "passive"))
      (node (ref "U$1") (pin "32") (pinfunction "MCLOCKI_32") (pintype "bidirectional"))
    )
    (net (code "59") (name "Net-(U$1-OSCO)") (class "Default")
      (node (ref "R21") (pin "2") (pinfunction "2_2") (pintype "passive"))
      (node (ref "U$1") (pin "31") (pinfunction "OSCO_31") (pintype "bidirectional"))
    )
    (net (code "60") (name "Net-(U$1-PLL_LF)") (class "Default")
      (node (ref "C34") (pin "2") (pinfunction "2_2") (pintype "passive"))
      (node (ref "C35") (pin "2") (pinfunction "2_2") (pintype "passive"))
      (node (ref "U$1") (pin "35") (pinfunction "PLL_LF_35") (pintype "bidirectional"))
    )
    (net (code "61") (name "Net-(U$1-VDRIVE)") (class "Default")
      (node (ref "R17") (pin "1") (pinfunction "1_1") (pintype "passive"))
      (node (ref "T1") (pin "B") (pinfunction "B_B") (pintype "passive"))
      (node (ref "U$1") (pin "17") (pinfunction "VDRIVE_17") (pintype "bidirectional"))
    )
    (net (code "62") (name "Net-(U$1-VOUT0)") (class "Default")
      (node (ref "R1") (pin "1") (pinfunction "1_1") (pintype "passive"))
      (node (ref "U$1") (pin "46") (pinfunction "VOUT0_46") (pintype "bidirectional"))
    )
    (net (code "63") (name "Net-(U$1-VOUT1)") (class "Default")
      (node (ref "R5") (pin "1") (pinfunction "1_1") (pintype "passive"))
      (node (ref "U$1") (pin "45") (pinfunction "VOUT1_45") (pintype "bidirectional"))
    )
    (net (code "64") (name "Net-(U$1-VOUT2)") (class "Default")
      (node (ref "R9") (pin "1") (pinfunction "1_1") (pintype "passive"))
      (node (ref "U$1") (pin "44") (pinfunction "VOUT2_44") (pintype "bidirectional"))
    )
    (net (code "65") (name "Net-(U$1-VOUT3)") (class "Default")
      (node (ref "R13") (pin "1") (pinfunction "1_1") (pintype "passive"))
      (node (ref "U$1") (pin "43") (pinfunction "VOUT3_43") (pintype "bidirectional"))
    )
    (net (code "66") (name "SCL") (class "Default")
      (node (ref "IC3") (pin "6") (pinfunction "SCL_6") (pintype "input"))
      (node (ref "JP1") (pin "4") (pinfunction "4_4") (pintype "passive"))
      (node (ref "R32") (pin "1") (pinfunction "1_1") (pintype "passive"))
      (node (ref "U$1") (pin "23") (pinfunction "SCL/CCLK_23") (pintype "bidirectional"))
    )
    (net (code "67") (name "SDA") (class "Default")
      (node (ref "IC3") (pin "5") (pinfunction "SDA_5") (pintype "bidirectional"))
      (node (ref "JP1") (pin "5") (pinfunction "5_5") (pintype "passive"))
      (node (ref "R33") (pin "1") (pinfunction "1_1") (pintype "passive"))
      (node (ref "U$1") (pin "22") (pinfunction "SDA/COUT_22") (pintype "bidirectional"))
    )
    (net (code "68") (name "WB") (class "Default")
      (node (ref "JP1") (pin "2") (pinfunction "2_2") (pintype "passive"))
      (node (ref "U$1") (pin "20") (pinfunction "ADR1/CDATA/WB_20") (pintype "bidirectional"))
    )
    (net (code "69") (name "WP") (class "Default")
      (node (ref "IC3") (pin "7") (pinfunction "WP_7") (pintype "input"))
      (node (ref "JP1") (pin "3") (pinfunction "3_3") (pintype "passive"))
      (node (ref "U$1") (pin "21") (pinfunction "CLATCH/WP_21") (pintype "bidirectional"))
    )
    (net (code "70") (name "unconnected-(X1-Pad2)") (class "Default")
      (node (ref "X1") (pin "2") (pinfunction "2_2") (pintype "passive"))
    )
    (net (code "71") (name "unconnected-(X1-Pad4)") (class "Default")
      (node (ref "X1") (pin "4") (pinfunction "4_4") (pintype "passive"))
    )
    (net (code "72") (name "unconnected-(X2-Pad2)") (class "Default")
      (node (ref "X2") (pin "2") (pinfunction "2_2") (pintype "passive"))
    )
    (net (code "73") (name "unconnected-(X2-Pad4)") (class "Default")
      (node (ref "X2") (pin "4") (pinfunction "4_4") (pintype "passive"))
    )
    (net (code "74") (name "unconnected-(X3-Pad2)") (class "Default")
      (node (ref "X3") (pin "2") (pinfunction "2_2") (pintype "passive"))
    )
    (net (code "75") (name "unconnected-(X3-Pad4)") (class "Default")
      (node (ref "X3") (pin "4") (pinfunction "4_4") (pintype "passive"))
    )
    (net (code "76") (name "unconnected-(X4-Pad2)") (class "Default")
      (node (ref "X4") (pin "2") (pinfunction "2_2") (pintype "input"))
    )
    (net (code "77") (name "unconnected-(X4-Pad3)") (class "Default")
      (node (ref "X4") (pin "3") (pinfunction "3_3") (pintype "input"))
    )
    (net (code "78") (name "unconnected-(X4-Pad4)") (class "Default")
      (node (ref "X4") (pin "4") (pinfunction "4_4") (pintype "input"))
    )
  )
)
